# PSOC_CY8C24123.net
KiCad netlist of a schematic drawn in EAGLE
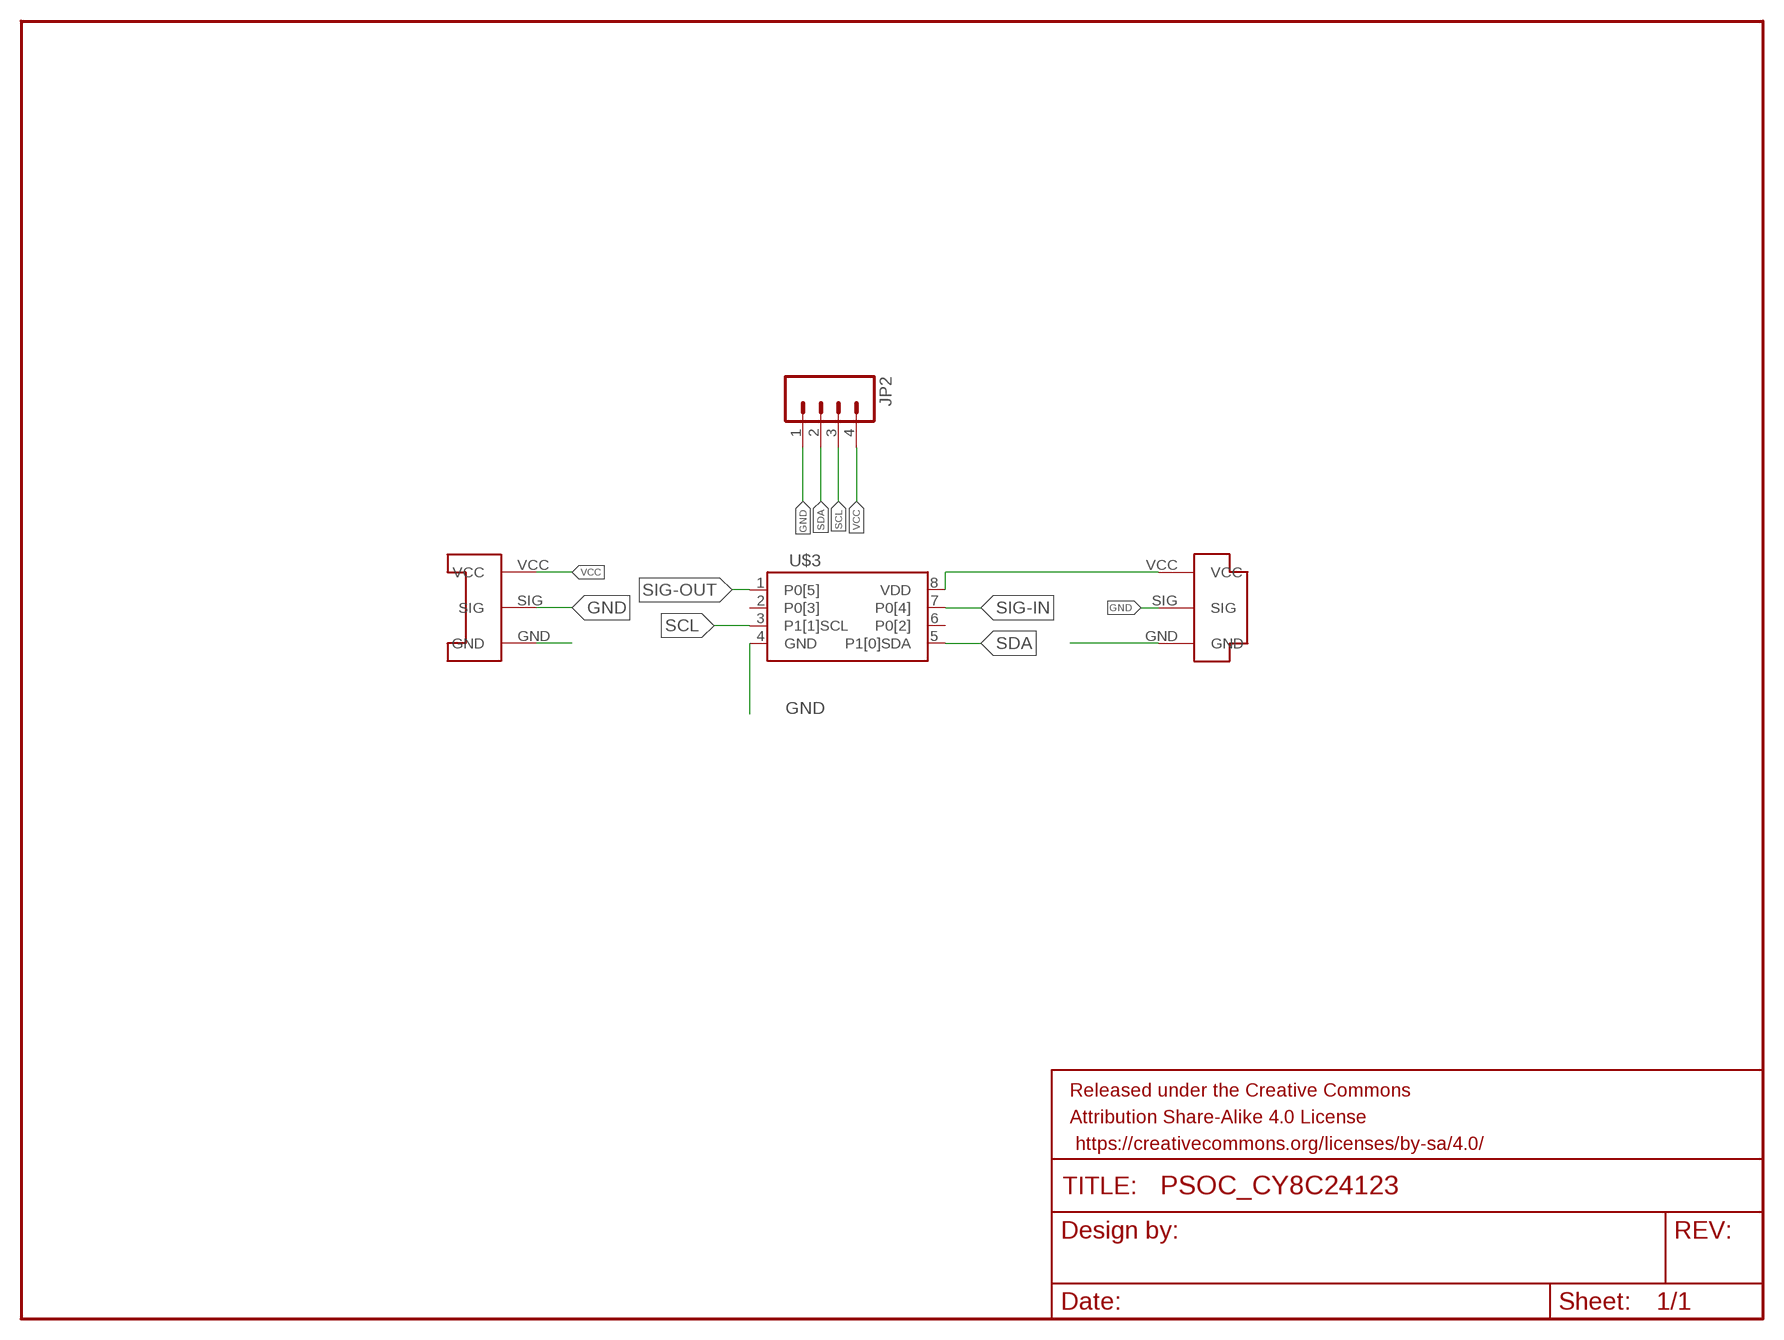
[diagram p0: schematic, sheet 1]

(export (version "E")
  (design (tool "Eeschema 10.0.6"))
  (components
    (comp (ref "FRAME1")
      (value "FRAME-LETTERNO_PACKAGE")
      (footprint "eagle-import:DUMMY")
      (fields (field (name "DESIGNER") "Nobody"))
      (libsource (lib "eagle-import") (part "FRAME-LETTERNO_PACKAGE"))
    )
    (comp (ref "JP2")
      (value "M041.27MM")
      (footprint "eagle-import:1X04-1.27MM")
      (libsource (lib "eagle-import") (part "M041.27MM"))
    )
    (comp (ref "U$1")
      (value "CONN-PLUG-3POS-3MM")
      (footprint "eagle-import:PLUG-3POS-3MM-SMD")
      (libsource (lib "eagle-import") (part "CONN-PLUG-3POS-3MM"))
    )
    (comp (ref "U$2")
      (value "CONN-SOCKET-3POS-3MM")
      (footprint "eagle-import:SOCKET-3POS-3MM-SMD")
      (libsource (lib "eagle-import") (part "CONN-SOCKET-3POS-3MM"))
    )
    (comp (ref "U$3")
      (value "CY8C24123A-24SXI")
      (footprint "eagle-import:SOIC8-PSOC1")
      (libsource (lib "eagle-import") (part "CY8C24123A-24SXI"))
    )
  )
  (nets
    (net (code "1") (name "GND") (class "Default")
      (node (ref "JP2") (pin "1") (pinfunction "VDD_1") (pintype "passive"))
      (node (ref "U$1") (pin "SIG") (pinfunction "SIG_SIG") (pintype "bidirectional"))
      (node (ref "U$2") (pin "SIG") (pinfunction "SIG_SIG") (pintype "bidirectional"))
      (node (ref "U$3") (pin "4") (pinfunction "GND_4") (pintype "power_in"))
    )
    (net (code "2") (name "SCL") (class "Default")
      (node (ref "JP2") (pin "3") (pinfunction "SIG-OUT_3") (pintype "passive"))
      (node (ref "U$3") (pin "3") (pinfunction "P1[1]SCL_3") (pintype "bidirectional"))
    )
    (net (code "3") (name "SDA") (class "Default")
      (node (ref "JP2") (pin "2") (pinfunction "COM-OUT_2") (pintype "passive"))
      (node (ref "U$3") (pin "5") (pinfunction "P1[0]SDA_5") (pintype "bidirectional"))
    )
    (net (code "4") (name "SIG-IN") (class "Default")
      (node (ref "U$2") (pin "GND") (pinfunction "GND_GND") (pintype "power_in"))
      (node (ref "U$3") (pin "7") (pinfunction "P0[4]_7") (pintype "bidirectional"))
    )
    (net (code "5") (name "SIG-OUT") (class "Default")
      (node (ref "U$1") (pin "GND") (pinfunction "GND_GND") (pintype "power_in"))
      (node (ref "U$3") (pin "1") (pinfunction "P0[5]_1") (pintype "bidirectional"))
    )
    (net (code "6") (name "VCC") (class "Default")
      (node (ref "JP2") (pin "4") (pinfunction "GND_4") (pintype "passive"))
      (node (ref "U$1") (pin "VCC") (pinfunction "VCC_VCC") (pintype "power_in"))
      (node (ref "U$2") (pin "VCC") (pinfunction "VCC_VCC") (pintype "power_in"))
      (node (ref "U$3") (pin "8") (pinfunction "VDD_8") (pintype "power_in"))
    )
    (net (code "7") (name "unconnected-(U$3-P0[2]-Pad6)") (class "Default")
      (node (ref "U$3") (pin "6") (pinfunction "P0[2]_6") (pintype "bidirectional"))
    )
    (net (code "8") (name "unconnected-(U$3-P0[3]-Pad2)") (class "Default")
      (node (ref "U$3") (pin "2") (pinfunction "P0[3]_2") (pintype "bidirectional"))
    )
  )
)
